# Rectifire__PFC__Evaluation_Board.net
KiCad netlist of a schematic drawn in Altium Designer
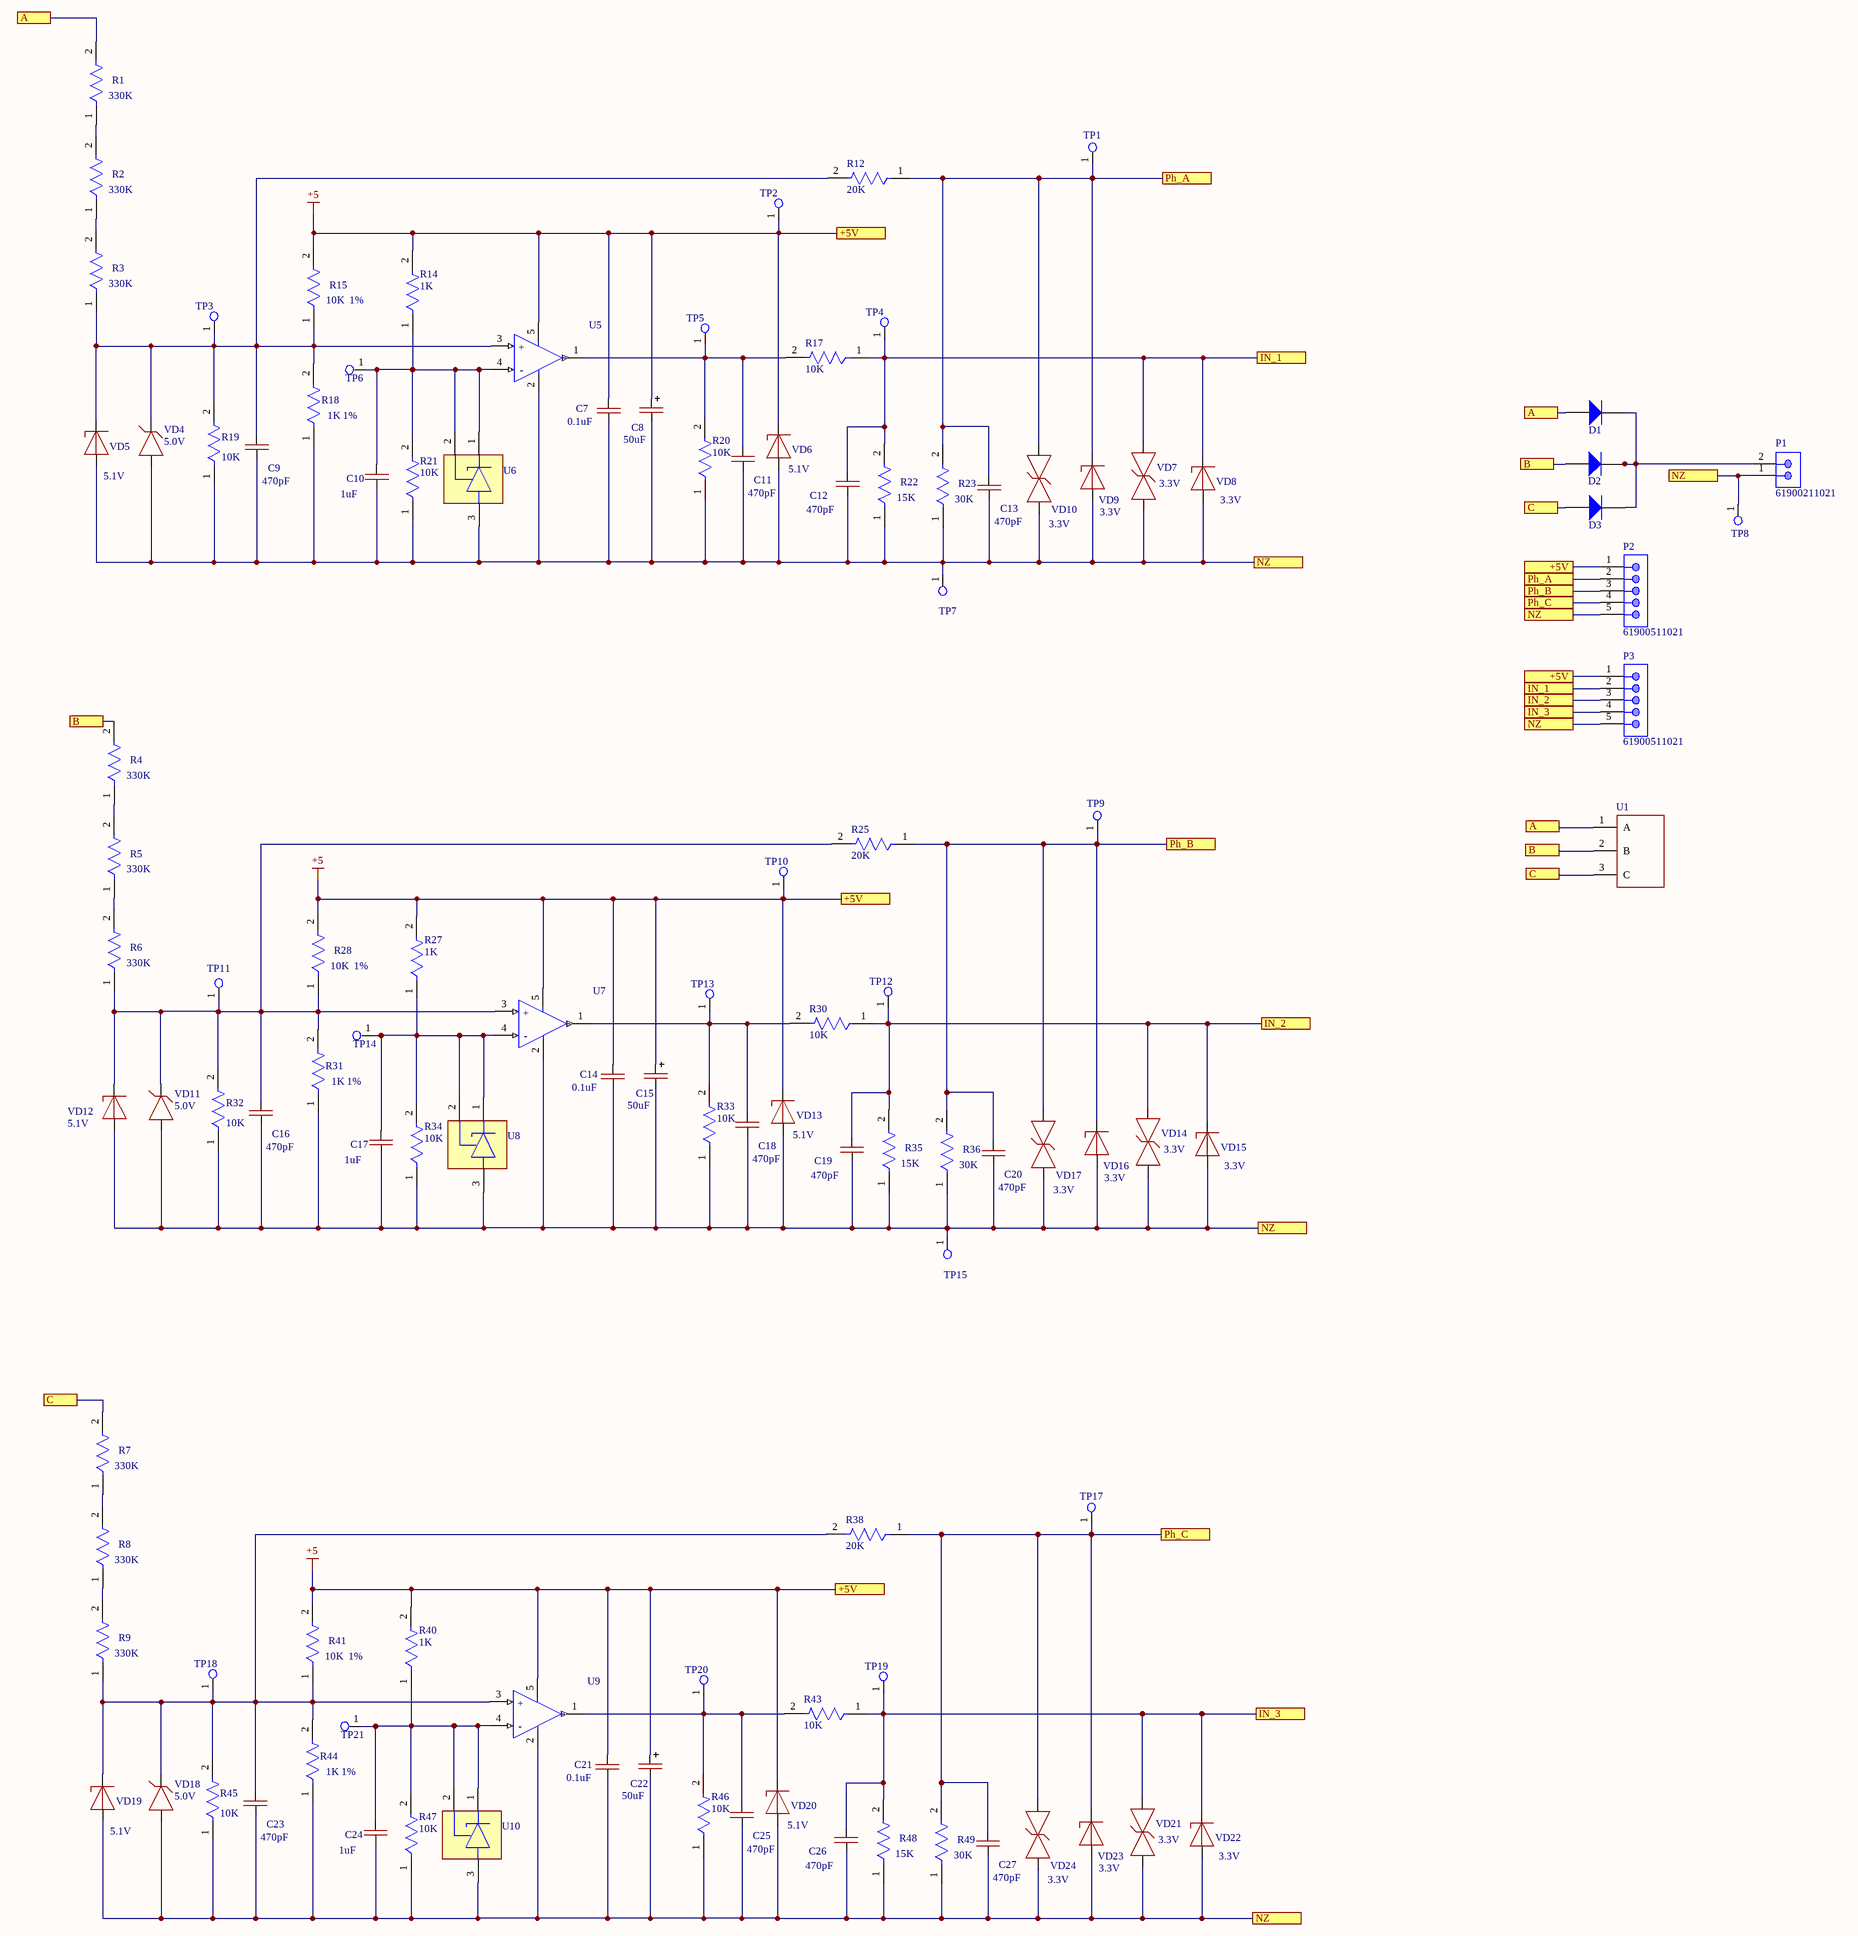
[diagram p0: Rectifire_(PFC)_Evaluation_Board.SchDoc]

(export (version "E")
  (design (tool "Eeschema 10.0.6"))
  (components
    (comp (ref "C7")
      (value "0.1uF")
      (footprint "CAP-0805")
      (libsource (lib "PASSIVE_COMPONENTS") (part "CAP-NON-POLAR"))
    )
    (comp (ref "C8")
      (value "50uF")
      (footprint "CAP-TAN-D")
      (libsource (lib "PASSIVE_COMPONENTS") (part "CAP-POLAR"))
    )
    (comp (ref "C9")
      (value "470pF")
      (footprint "CAP-0805")
      (libsource (lib "PASSIVE_COMPONENTS") (part "CAP-NON-POLAR"))
    )
    (comp (ref "C10")
      (value "1uF")
      (footprint "CAP-0805")
      (libsource (lib "PASSIVE_COMPONENTS") (part "CAP-NON-POLAR"))
    )
    (comp (ref "C11")
      (value "470pF")
      (footprint "CAP-0805")
      (libsource (lib "PASSIVE_COMPONENTS") (part "CAP-NON-POLAR"))
    )
    (comp (ref "C12")
      (value "470pF")
      (footprint "CAP-0805")
      (libsource (lib "PASSIVE_COMPONENTS") (part "CAP-NON-POLAR"))
    )
    (comp (ref "C13")
      (value "470pF")
      (footprint "CAP-0805")
      (libsource (lib "PASSIVE_COMPONENTS") (part "CAP-NON-POLAR"))
    )
    (comp (ref "C14")
      (value "0.1uF")
      (footprint "CAP-0805")
      (libsource (lib "PASSIVE_COMPONENTS") (part "CAP-NON-POLAR"))
    )
    (comp (ref "C15")
      (value "50uF")
      (footprint "CAP-TAN-D")
      (libsource (lib "PASSIVE_COMPONENTS") (part "CAP-POLAR"))
    )
    (comp (ref "C16")
      (value "470pF")
      (footprint "CAP-0805")
      (libsource (lib "PASSIVE_COMPONENTS") (part "CAP-NON-POLAR"))
    )
    (comp (ref "C17")
      (value "1uF")
      (footprint "CAP-0805")
      (libsource (lib "PASSIVE_COMPONENTS") (part "CAP-NON-POLAR"))
    )
    (comp (ref "C18")
      (value "470pF")
      (footprint "CAP-0805")
      (libsource (lib "PASSIVE_COMPONENTS") (part "CAP-NON-POLAR"))
    )
    (comp (ref "C19")
      (value "470pF")
      (footprint "CAP-0805")
      (libsource (lib "PASSIVE_COMPONENTS") (part "CAP-NON-POLAR"))
    )
    (comp (ref "C20")
      (value "470pF")
      (footprint "CAP-0805")
      (libsource (lib "PASSIVE_COMPONENTS") (part "CAP-NON-POLAR"))
    )
    (comp (ref "C21")
      (value "0.1uF")
      (footprint "CAP-0805")
      (libsource (lib "PASSIVE_COMPONENTS") (part "CAP-NON-POLAR"))
    )
    (comp (ref "C22")
      (value "50uF")
      (footprint "CAP-TAN-D")
      (libsource (lib "PASSIVE_COMPONENTS") (part "CAP-POLAR"))
    )
    (comp (ref "C23")
      (value "470pF")
      (footprint "CAP-0805")
      (libsource (lib "PASSIVE_COMPONENTS") (part "CAP-NON-POLAR"))
    )
    (comp (ref "C24")
      (value "1uF")
      (footprint "CAP-0805")
      (libsource (lib "PASSIVE_COMPONENTS") (part "CAP-NON-POLAR"))
    )
    (comp (ref "C25")
      (value "470pF")
      (footprint "CAP-0805")
      (libsource (lib "PASSIVE_COMPONENTS") (part "CAP-NON-POLAR"))
    )
    (comp (ref "C26")
      (value "470pF")
      (footprint "CAP-0805")
      (libsource (lib "PASSIVE_COMPONENTS") (part "CAP-NON-POLAR"))
    )
    (comp (ref "C27")
      (value "470pF")
      (footprint "CAP-0805")
      (libsource (lib "PASSIVE_COMPONENTS") (part "CAP-NON-POLAR"))
    )
    (comp (ref "D1")
      (value "FR-207")
      (footprint "FP-DO-201AD-MFG")
      (description "FR207")
      (libsource (lib "Diodes") (part "FR-207"))
    )
    (comp (ref "D2")
      (value "FR-207")
      (footprint "FP-DO-201AD-MFG")
      (description "FR207")
      (libsource (lib "Diodes") (part "FR-207"))
    )
    (comp (ref "D3")
      (value "FR-207")
      (footprint "FP-DO-201AD-MFG")
      (description "FR207")
      (libsource (lib "Diodes") (part "FR-207"))
    )
    (comp (ref "P1")
      (value "61900211021")
      (footprint "61900211021")
      (description "WR-WTB THT Male Left Angled Bottom Locking Header, pitch 2.54mm, 2p")
      (fields (field (name "PUBLISHER") "Wurth Elektronik"))
      (libsource (lib "Altium_WR-WTB (rev20a)") (part "61900211021"))
    )
    (comp (ref "P2")
      (value "61900511021")
      (footprint "61900511021")
      (description "WR-WTB THT Male Left Angled Bottom Locking Header, pitch 2.54mm, 5p")
      (fields (field (name "PUBLISHER") "Wurth Elektronik"))
      (libsource (lib "Altium_WR-WTB (rev20a)") (part "61900511021"))
    )
    (comp (ref "P3")
      (value "61900511021")
      (footprint "61900511021")
      (description "WR-WTB THT Male Left Angled Bottom Locking Header, pitch 2.54mm, 5p")
      (fields (field (name "PUBLISHER") "Wurth Elektronik"))
      (libsource (lib "Altium_WR-WTB (rev20a)") (part "61900511021"))
    )
    (comp (ref "R1")
      (value "330K")
      (footprint "RES-1206")
      (description "10K")
      (libsource (lib "PASSIVE_COMPONENTS") (part "RES-CONST"))
    )
    (comp (ref "R2")
      (value "330K")
      (footprint "RES-1206")
      (description "10K")
      (libsource (lib "PASSIVE_COMPONENTS") (part "RES-CONST"))
    )
    (comp (ref "R3")
      (value "330K")
      (footprint "RES-1206")
      (description "10K")
      (libsource (lib "PASSIVE_COMPONENTS") (part "RES-CONST"))
    )
    (comp (ref "R4")
      (value "330K")
      (footprint "RES-1206")
      (description "10K")
      (libsource (lib "PASSIVE_COMPONENTS") (part "RES-CONST"))
    )
    (comp (ref "R5")
      (value "330K")
      (footprint "RES-1206")
      (description "10K")
      (libsource (lib "PASSIVE_COMPONENTS") (part "RES-CONST"))
    )
    (comp (ref "R6")
      (value "330K")
      (footprint "RES-1206")
      (description "10K")
      (libsource (lib "PASSIVE_COMPONENTS") (part "RES-CONST"))
    )
    (comp (ref "R7")
      (value "330K")
      (footprint "RES-1206")
      (description "10K")
      (libsource (lib "PASSIVE_COMPONENTS") (part "RES-CONST"))
    )
    (comp (ref "R8")
      (value "330K")
      (footprint "RES-1206")
      (description "10K")
      (libsource (lib "PASSIVE_COMPONENTS") (part "RES-CONST"))
    )
    (comp (ref "R9")
      (value "330K")
      (footprint "RES-1206")
      (description "10K")
      (libsource (lib "PASSIVE_COMPONENTS") (part "RES-CONST"))
    )
    (comp (ref "R12")
      (value "20K")
      (footprint "RES-0805")
      (libsource (lib "PASSIVE_COMPONENTS") (part "RES-CONST"))
    )
    (comp (ref "R14")
      (value "1K")
      (footprint "RES-0805")
      (description "4.7K")
      (libsource (lib "PASSIVE_COMPONENTS") (part "RES-CONST"))
    )
    (comp (ref "R15")
      (value "10K  1%")
      (footprint "RES-0805")
      (description "10K")
      (libsource (lib "PASSIVE_COMPONENTS") (part "RES-CONST"))
    )
    (comp (ref "R17")
      (value "10K")
      (footprint "RES-0805")
      (libsource (lib "PASSIVE_COMPONENTS") (part "RES-CONST"))
    )
    (comp (ref "R18")
      (value "1K 1%")
      (footprint "RES-0805")
      (description "1K")
      (libsource (lib "PASSIVE_COMPONENTS") (part "RES-CONST"))
    )
    (comp (ref "R19")
      (value "10K")
      (footprint "RES_SMD_1210_IPC_B")
      (libsource (lib "PASSIVE_COMPONENTS") (part "RES_1210"))
    )
    (comp (ref "R20")
      (value "10K")
      (footprint "RES-0805")
      (libsource (lib "PASSIVE_COMPONENTS") (part "RES-CONST"))
    )
    (comp (ref "R21")
      (value "10K")
      (footprint "RES-0805")
      (libsource (lib "PASSIVE_COMPONENTS") (part "RES-CONST"))
    )
    (comp (ref "R22")
      (value "15K")
      (footprint "RES-0805")
      (libsource (lib "PASSIVE_COMPONENTS") (part "RES-CONST"))
    )
    (comp (ref "R23")
      (value "30K")
      (footprint "RES-0805")
      (libsource (lib "PASSIVE_COMPONENTS") (part "RES-CONST"))
    )
    (comp (ref "R25")
      (value "20K")
      (footprint "RES-0805")
      (libsource (lib "PASSIVE_COMPONENTS") (part "RES-CONST"))
    )
    (comp (ref "R27")
      (value "1K")
      (footprint "RES-0805")
      (description "4.7K")
      (libsource (lib "PASSIVE_COMPONENTS") (part "RES-CONST"))
    )
    (comp (ref "R28")
      (value "10K  1%")
      (footprint "RES-0805")
      (description "10K")
      (libsource (lib "PASSIVE_COMPONENTS") (part "RES-CONST"))
    )
    (comp (ref "R30")
      (value "10K")
      (footprint "RES-0805")
      (libsource (lib "PASSIVE_COMPONENTS") (part "RES-CONST"))
    )
    (comp (ref "R31")
      (value "1K 1%")
      (footprint "RES-0805")
      (description "1K")
      (libsource (lib "PASSIVE_COMPONENTS") (part "RES-CONST"))
    )
    (comp (ref "R32")
      (value "10K")
      (footprint "RES_SMD_1210_IPC_B")
      (libsource (lib "PASSIVE_COMPONENTS") (part "RES_1210"))
    )
    (comp (ref "R33")
      (value "10K")
      (footprint "RES-0805")
      (libsource (lib "PASSIVE_COMPONENTS") (part "RES-CONST"))
    )
    (comp (ref "R34")
      (value "10K")
      (footprint "RES-0805")
      (libsource (lib "PASSIVE_COMPONENTS") (part "RES-CONST"))
    )
    (comp (ref "R35")
      (value "15K")
      (footprint "RES-0805")
      (libsource (lib "PASSIVE_COMPONENTS") (part "RES-CONST"))
    )
    (comp (ref "R36")
      (value "30K")
      (footprint "RES-0805")
      (libsource (lib "PASSIVE_COMPONENTS") (part "RES-CONST"))
    )
    (comp (ref "R38")
      (value "20K")
      (footprint "RES-0805")
      (libsource (lib "PASSIVE_COMPONENTS") (part "RES-CONST"))
    )
    (comp (ref "R40")
      (value "1K")
      (footprint "RES-0805")
      (description "4.7K")
      (libsource (lib "PASSIVE_COMPONENTS") (part "RES-CONST"))
    )
    (comp (ref "R41")
      (value "10K  1%")
      (footprint "RES-0805")
      (description "10K")
      (libsource (lib "PASSIVE_COMPONENTS") (part "RES-CONST"))
    )
    (comp (ref "R43")
      (value "10K")
      (footprint "RES-0805")
      (libsource (lib "PASSIVE_COMPONENTS") (part "RES-CONST"))
    )
    (comp (ref "R44")
      (value "1K 1%")
      (footprint "RES-0805")
      (description "1K")
      (libsource (lib "PASSIVE_COMPONENTS") (part "RES-CONST"))
    )
    (comp (ref "R45")
      (value "10K")
      (footprint "RES_SMD_1210_IPC_B")
      (libsource (lib "PASSIVE_COMPONENTS") (part "RES_1210"))
    )
    (comp (ref "R46")
      (value "10K")
      (footprint "RES-0805")
      (libsource (lib "PASSIVE_COMPONENTS") (part "RES-CONST"))
    )
    (comp (ref "R47")
      (value "10K")
      (footprint "RES-0805")
      (libsource (lib "PASSIVE_COMPONENTS") (part "RES-CONST"))
    )
    (comp (ref "R48")
      (value "15K")
      (footprint "RES-0805")
      (libsource (lib "PASSIVE_COMPONENTS") (part "RES-CONST"))
    )
    (comp (ref "R49")
      (value "30K")
      (footprint "RES-0805")
      (libsource (lib "PASSIVE_COMPONENTS") (part "RES-CONST"))
    )
    (comp (ref "TP1")
      (value "Test_Point_PCB")
      (footprint "Test_Point")
      (description "Test_Point")
      (libsource (lib "Connectors") (part "TP_PCB?"))
    )
    (comp (ref "TP2")
      (value "Test_Point_PCB")
      (footprint "Test_Point")
      (description "Test_Point")
      (libsource (lib "Connectors") (part "TP_PCB?"))
    )
    (comp (ref "TP3")
      (value "Test_Point_PCB")
      (footprint "Test_Point")
      (description "Test_Point")
      (libsource (lib "Connectors") (part "TP_PCB?"))
    )
    (comp (ref "TP4")
      (value "Test_Point_PCB")
      (footprint "Test_Point")
      (description "Test_Point")
      (libsource (lib "Connectors") (part "TP_PCB?"))
    )
    (comp (ref "TP5")
      (value "Test_Point_PCB")
      (footprint "Test_Point")
      (description "Test_Point")
      (libsource (lib "Connectors") (part "TP_PCB?"))
    )
    (comp (ref "TP6")
      (value "Test_Point_PCB")
      (footprint "Test_Point")
      (description "Test_Point")
      (libsource (lib "Connectors") (part "TP_PCB?"))
    )
    (comp (ref "TP7")
      (value "Test_Point_PCB")
      (footprint "Test_Point")
      (description "Test_Point")
      (libsource (lib "Connectors") (part "TP_PCB?"))
    )
    (comp (ref "TP8")
      (value "Test_Point_PCB")
      (footprint "Test_Point")
      (description "Test_Point")
      (libsource (lib "Connectors") (part "TP_PCB?"))
    )
    (comp (ref "TP9")
      (value "Test_Point_PCB")
      (footprint "Test_Point")
      (description "Test_Point")
      (libsource (lib "Connectors") (part "TP_PCB?"))
    )
    (comp (ref "TP10")
      (value "Test_Point_PCB")
      (footprint "Test_Point")
      (description "Test_Point")
      (libsource (lib "Connectors") (part "TP_PCB?"))
    )
    (comp (ref "TP11")
      (value "Test_Point_PCB")
      (footprint "Test_Point")
      (description "Test_Point")
      (libsource (lib "Connectors") (part "TP_PCB?"))
    )
    (comp (ref "TP12")
      (value "Test_Point_PCB")
      (footprint "Test_Point")
      (description "Test_Point")
      (libsource (lib "Connectors") (part "TP_PCB?"))
    )
    (comp (ref "TP13")
      (value "Test_Point_PCB")
      (footprint "Test_Point")
      (description "Test_Point")
      (libsource (lib "Connectors") (part "TP_PCB?"))
    )
    (comp (ref "TP14")
      (value "Test_Point_PCB")
      (footprint "Test_Point")
      (description "Test_Point")
      (libsource (lib "Connectors") (part "TP_PCB?"))
    )
    (comp (ref "TP15")
      (value "Test_Point_PCB")
      (footprint "Test_Point")
      (description "Test_Point")
      (libsource (lib "Connectors") (part "TP_PCB?"))
    )
    (comp (ref "TP17")
      (value "Test_Point_PCB")
      (footprint "Test_Point")
      (description "Test_Point")
      (libsource (lib "Connectors") (part "TP_PCB?"))
    )
    (comp (ref "TP18")
      (value "~")
      (footprint "Test_Point")
      (description "Test_Point")
      (libsource (lib "Connectors") (part "TP_PCB?"))
    )
    (comp (ref "TP19")
      (value "~")
      (footprint "Test_Point")
      (description "Test_Point")
      (libsource (lib "Connectors") (part "TP_PCB?"))
    )
    (comp (ref "TP20")
      (value "Test_Point_PCB")
      (footprint "Test_Point")
      (description "Test_Point")
      (libsource (lib "Connectors") (part "TP_PCB?"))
    )
    (comp (ref "TP21")
      (value "Test_Point_PCB")
      (footprint "Test_Point")
      (description "Test_Point")
      (libsource (lib "Connectors") (part "TP_PCB?"))
    )
    (comp (ref "U1") (value "~") (footprint "MDS100") (libsource (lib "MDS100") (part "MDS100")))
    (comp (ref "U5")
      (value "~")
      (footprint "SOT-23-5")
      (description "IC OPAMP GP 1 CIRCUIT SOT23-5")
      (fields (field (name "VOLTAGE") "6V"))
      (libsource (lib "Integrated_Circuts") (part "MCP6001T"))
    )
    (comp (ref "U6")
      (value "TL431")
      (footprint "TL431_SOT-23-3(A)")
      (description "TL431_SOT-23-3")
      (libsource (lib "Diodes") (part "TL431_SOT-23-3"))
    )
    (comp (ref "U7")
      (value "~")
      (footprint "SOT-23-5")
      (description "IC OPAMP GP 1 CIRCUIT SOT23-5")
      (fields (field (name "VOLTAGE") "6V"))
      (libsource (lib "Integrated_Circuts") (part "MCP6001T"))
    )
    (comp (ref "U8")
      (value "TL431")
      (footprint "TL431_SOT-23-3(A)")
      (description "TL431_SOT-23-3")
      (libsource (lib "Diodes") (part "TL431_SOT-23-3"))
    )
    (comp (ref "U9")
      (value "~")
      (footprint "SOT-23-5")
      (description "IC OPAMP GP 1 CIRCUIT SOT23-5")
      (fields (field (name "VOLTAGE") "6V"))
      (libsource (lib "Integrated_Circuts") (part "MCP6001T"))
    )
    (comp (ref "U10")
      (value "TL431")
      (footprint "TL431_SOT-23-3(A)")
      (description "TL431_SOT-23-3")
      (libsource (lib "Diodes") (part "TL431_SOT-23-3"))
    )
    (comp (ref "VD4") (value "5.0V") (footprint "SOD-323") (libsource (lib "Diodes") (part "SMBJ15A")))
    (comp (ref "VD5") (value "5.1V") (footprint "DIOD-SOD123-2_V") (libsource (lib "Diodes") (part "ZENER")))
    (comp (ref "VD6") (value "5.1V") (footprint "DIOD-SOD123-2_V") (libsource (lib "Diodes") (part "ZENER")))
    (comp (ref "VD7") (value "3.3V") (footprint "DO-214AA") (libsource (lib "Diodes") (part "Suppressor")))
    (comp (ref "VD8") (value "3.3V") (footprint "DIOD-SOD123-2_V") (libsource (lib "Diodes") (part "ZENER")))
    (comp (ref "VD9") (value "3.3V") (footprint "DIOD-SOD123-2_V") (libsource (lib "Diodes") (part "ZENER")))
    (comp (ref "VD10") (value "3.3V") (footprint "DO-214AA") (libsource (lib "Diodes") (part "Suppressor")))
    (comp (ref "VD11") (value "5.0V") (footprint "SOD-323") (libsource (lib "Diodes") (part "SMBJ15A")))
    (comp (ref "VD12") (value "5.1V") (footprint "DIOD-SOD123-2_V") (libsource (lib "Diodes") (part "ZENER")))
    (comp (ref "VD13") (value "5.1V") (footprint "DIOD-SOD123-2_V") (libsource (lib "Diodes") (part "ZENER")))
    (comp (ref "VD14") (value "3.3V") (footprint "DO-214AA") (libsource (lib "Diodes") (part "Suppressor")))
    (comp (ref "VD15") (value "3.3V") (footprint "DIOD-SOD123-2_V") (libsource (lib "Diodes") (part "ZENER")))
    (comp (ref "VD16") (value "3.3V") (footprint "DIOD-SOD123-2_V") (libsource (lib "Diodes") (part "ZENER")))
    (comp (ref "VD17") (value "3.3V") (footprint "DO-214AA") (libsource (lib "Diodes") (part "Suppressor")))
    (comp (ref "VD18") (value "5.0V") (footprint "SOD-323") (libsource (lib "Diodes") (part "SMBJ15A")))
    (comp (ref "VD19") (value "5.1V") (footprint "DIOD-SOD123-2_V") (libsource (lib "Diodes") (part "ZENER")))
    (comp (ref "VD20") (value "5.1V") (footprint "DIOD-SOD123-2_V") (libsource (lib "Diodes") (part "ZENER")))
    (comp (ref "VD21") (value "3.3V") (footprint "DO-214AA") (libsource (lib "Diodes") (part "Suppressor")))
    (comp (ref "VD22") (value "3.3V") (footprint "DIOD-SOD123-2_V") (libsource (lib "Diodes") (part "ZENER")))
    (comp (ref "VD23") (value "3.3V") (footprint "DIOD-SOD123-2_V") (libsource (lib "Diodes") (part "ZENER")))
    (comp (ref "VD24") (value "3.3V") (footprint "DO-214AA") (libsource (lib "Diodes") (part "Suppressor")))
  )
  (nets
    (net (code "1") (name "+5") (class "Default")
      (node (ref "C14") (pin "2") (pinfunction "2_2") (pintype "passive"))
      (node (ref "C15") (pin "1") (pinfunction "+_1") (pintype "passive"))
      (node (ref "C21") (pin "2") (pinfunction "2_2") (pintype "passive"))
      (node (ref "C22") (pin "1") (pinfunction "+_1") (pintype "passive"))
      (node (ref "C7") (pin "2") (pinfunction "2_2") (pintype "passive"))
      (node (ref "C8") (pin "1") (pinfunction "+_1") (pintype "passive"))
      (node (ref "P2") (pin "1") (pinfunction "1_1") (pintype "passive"))
      (node (ref "P3") (pin "1") (pinfunction "1_1") (pintype "passive"))
      (node (ref "R14") (pin "2") (pinfunction "2_2") (pintype "passive"))
      (node (ref "R15") (pin "2") (pinfunction "2_2") (pintype "passive"))
      (node (ref "R27") (pin "2") (pinfunction "2_2") (pintype "passive"))
      (node (ref "R28") (pin "2") (pinfunction "2_2") (pintype "passive"))
      (node (ref "R40") (pin "2") (pinfunction "2_2") (pintype "passive"))
      (node (ref "R41") (pin "2") (pinfunction "2_2") (pintype "passive"))
      (node (ref "TP10") (pin "1") (pinfunction "G9_1") (pintype "passive"))
      (node (ref "TP2") (pin "1") (pinfunction "G9_1") (pintype "passive"))
      (node (ref "U5") (pin "5") (pinfunction "VDD_5") (pintype "power_in"))
      (node (ref "U7") (pin "5") (pinfunction "VDD_5") (pintype "power_in"))
      (node (ref "U9") (pin "5") (pinfunction "VDD_5") (pintype "power_in"))
      (node (ref "VD13") (pin "1") (pinfunction "C_1") (pintype "passive"))
      (node (ref "VD20") (pin "1") (pinfunction "C_1") (pintype "passive"))
      (node (ref "VD6") (pin "1") (pinfunction "C_1") (pintype "passive"))
    )
    (net (code "2") (name "/A") (class "Default")
      (node (ref "D1") (pin "2") (pinfunction "A_2") (pintype "passive"))
      (node (ref "R1") (pin "2") (pinfunction "2_2") (pintype "passive"))
      (node (ref "U1") (pin "1") (pinfunction "A_1") (pintype "tri_state"))
    )
    (net (code "3") (name "/B") (class "Default")
      (node (ref "D2") (pin "2") (pinfunction "A_2") (pintype "passive"))
      (node (ref "R4") (pin "2") (pinfunction "2_2") (pintype "passive"))
      (node (ref "U1") (pin "2") (pinfunction "B_2") (pintype "tri_state"))
    )
    (net (code "4") (name "/C") (class "Default")
      (node (ref "D3") (pin "2") (pinfunction "A_2") (pintype "passive"))
      (node (ref "R7") (pin "2") (pinfunction "2_2") (pintype "passive"))
      (node (ref "U1") (pin "3") (pinfunction "C_3") (pintype "tri_state"))
    )
    (net (code "5") (name "/IN_1") (class "Default")
      (node (ref "C12") (pin "2") (pinfunction "2_2") (pintype "passive"))
      (node (ref "P3") (pin "2") (pinfunction "2_2") (pintype "passive"))
      (node (ref "R17") (pin "1") (pinfunction "1_1") (pintype "passive"))
      (node (ref "R22") (pin "2") (pinfunction "2_2") (pintype "passive"))
      (node (ref "TP4") (pin "1") (pinfunction "G9_1") (pintype "passive"))
      (node (ref "VD7") (pin "2") (pinfunction "A_2") (pintype "passive"))
      (node (ref "VD8") (pin "1") (pinfunction "C_1") (pintype "passive"))
    )
    (net (code "6") (name "/IN_2") (class "Default")
      (node (ref "C19") (pin "2") (pinfunction "2_2") (pintype "passive"))
      (node (ref "P3") (pin "3") (pinfunction "3_3") (pintype "passive"))
      (node (ref "R30") (pin "1") (pinfunction "1_1") (pintype "passive"))
      (node (ref "R35") (pin "2") (pinfunction "2_2") (pintype "passive"))
      (node (ref "TP12") (pin "1") (pinfunction "G9_1") (pintype "passive"))
      (node (ref "VD14") (pin "2") (pinfunction "A_2") (pintype "passive"))
      (node (ref "VD15") (pin "1") (pinfunction "C_1") (pintype "passive"))
    )
    (net (code "7") (name "/IN_3") (class "Default")
      (node (ref "C26") (pin "2") (pinfunction "2_2") (pintype "passive"))
      (node (ref "P3") (pin "4") (pinfunction "4_4") (pintype "passive"))
      (node (ref "R43") (pin "1") (pinfunction "1_1") (pintype "passive"))
      (node (ref "R48") (pin "2") (pinfunction "2_2") (pintype "passive"))
      (node (ref "TP19") (pin "1") (pinfunction "G9_1") (pintype "passive"))
      (node (ref "VD21") (pin "2") (pinfunction "A_2") (pintype "passive"))
      (node (ref "VD22") (pin "1") (pinfunction "C_1") (pintype "passive"))
    )
    (net (code "8") (name "/NZ") (class "Default")
      (node (ref "C10") (pin "1") (pinfunction "1_1") (pintype "passive"))
      (node (ref "C11") (pin "1") (pinfunction "1_1") (pintype "passive"))
      (node (ref "C12") (pin "1") (pinfunction "1_1") (pintype "passive"))
      (node (ref "C13") (pin "1") (pinfunction "1_1") (pintype "passive"))
      (node (ref "C14") (pin "1") (pinfunction "1_1") (pintype "passive"))
      (node (ref "C15") (pin "2") (pinfunction "-_2") (pintype "passive"))
      (node (ref "C16") (pin "1") (pinfunction "1_1") (pintype "passive"))
      (node (ref "C17") (pin "1") (pinfunction "1_1") (pintype "passive"))
      (node (ref "C18") (pin "1") (pinfunction "1_1") (pintype "passive"))
      (node (ref "C19") (pin "1") (pinfunction "1_1") (pintype "passive"))
      (node (ref "C20") (pin "1") (pinfunction "1_1") (pintype "passive"))
      (node (ref "C21") (pin "1") (pinfunction "1_1") (pintype "passive"))
      (node (ref "C22") (pin "2") (pinfunction "-_2") (pintype "passive"))
      (node (ref "C23") (pin "1") (pinfunction "1_1") (pintype "passive"))
      (node (ref "C24") (pin "1") (pinfunction "1_1") (pintype "passive"))
      (node (ref "C25") (pin "1") (pinfunction "1_1") (pintype "passive"))
      (node (ref "C26") (pin "1") (pinfunction "1_1") (pintype "passive"))
      (node (ref "C27") (pin "1") (pinfunction "1_1") (pintype "passive"))
      (node (ref "C7") (pin "1") (pinfunction "1_1") (pintype "passive"))
      (node (ref "C8") (pin "2") (pinfunction "-_2") (pintype "passive"))
      (node (ref "C9") (pin "1") (pinfunction "1_1") (pintype "passive"))
      (node (ref "P1") (pin "1") (pinfunction "1_1") (pintype "passive"))
      (node (ref "P2") (pin "5") (pinfunction "5_5") (pintype "passive"))
      (node (ref "P3") (pin "5") (pinfunction "5_5") (pintype "passive"))
      (node (ref "R18") (pin "1") (pinfunction "1_1") (pintype "passive"))
      (node (ref "R19") (pin "1") (pinfunction "1_1") (pintype "passive"))
      (node (ref "R20") (pin "1") (pinfunction "1_1") (pintype "passive"))
      (node (ref "R21") (pin "1") (pinfunction "1_1") (pintype "passive"))
      (node (ref "R22") (pin "1") (pinfunction "1_1") (pintype "passive"))
      (node (ref "R23") (pin "1") (pinfunction "1_1") (pintype "passive"))
      (node (ref "R31") (pin "1") (pinfunction "1_1") (pintype "passive"))
      (node (ref "R32") (pin "1") (pinfunction "1_1") (pintype "passive"))
      (node (ref "R33") (pin "1") (pinfunction "1_1") (pintype "passive"))
      (node (ref "R34") (pin "1") (pinfunction "1_1") (pintype "passive"))
      (node (ref "R35") (pin "1") (pinfunction "1_1") (pintype "passive"))
      (node (ref "R36") (pin "1") (pinfunction "1_1") (pintype "passive"))
      (node (ref "R44") (pin "1") (pinfunction "1_1") (pintype "passive"))
      (node (ref "R45") (pin "1") (pinfunction "1_1") (pintype "passive"))
      (node (ref "R46") (pin "1") (pinfunction "1_1") (pintype "passive"))
      (node (ref "R47") (pin "1") (pinfunction "1_1") (pintype "passive"))
      (node (ref "R48") (pin "1") (pinfunction "1_1") (pintype "passive"))
      (node (ref "R49") (pin "1") (pinfunction "1_1") (pintype "passive"))
      (node (ref "TP15") (pin "1") (pinfunction "G9_1") (pintype "passive"))
      (node (ref "TP7") (pin "1") (pinfunction "G9_1") (pintype "passive"))
      (node (ref "TP8") (pin "1") (pinfunction "G9_1") (pintype "passive"))
      (node (ref "U10") (pin "3") (pinfunction "A_3") (pintype "passive"))
      (node (ref "U5") (pin "2") (pinfunction "VSS_2") (pintype "power_in"))
      (node (ref "U6") (pin "3") (pinfunction "A_3") (pintype "passive"))
      (node (ref "U7") (pin "2") (pinfunction "VSS_2") (pintype "power_in"))
      (node (ref "U8") (pin "3") (pinfunction "A_3") (pintype "passive"))
      (node (ref "U9") (pin "2") (pinfunction "VSS_2") (pintype "power_in"))
      (node (ref "VD10") (pin "1") (pinfunction "C_1") (pintype "passive"))
      (node (ref "VD11") (pin "1") (pinfunction "A_1") (pintype "passive"))
      (node (ref "VD12") (pin "2") (pinfunction "A_2") (pintype "passive"))
      (node (ref "VD13") (pin "2") (pinfunction "A_2") (pintype "passive"))
      (node (ref "VD14") (pin "1") (pinfunction "C_1") (pintype "passive"))
      (node (ref "VD15") (pin "2") (pinfunction "A_2") (pintype "passive"))
      (node (ref "VD16") (pin "2") (pinfunction "A_2") (pintype "passive"))
      (node (ref "VD17") (pin "1") (pinfunction "C_1") (pintype "passive"))
      (node (ref "VD18") (pin "1") (pinfunction "A_1") (pintype "passive"))
      (node (ref "VD19") (pin "2") (pinfunction "A_2") (pintype "passive"))
      (node (ref "VD20") (pin "2") (pinfunction "A_2") (pintype "passive"))
      (node (ref "VD21") (pin "1") (pinfunction "C_1") (pintype "passive"))
      (node (ref "VD22") (pin "2") (pinfunction "A_2") (pintype "passive"))
      (node (ref "VD23") (pin "2") (pinfunction "A_2") (pintype "passive"))
      (node (ref "VD24") (pin "1") (pinfunction "C_1") (pintype "passive"))
      (node (ref "VD4") (pin "1") (pinfunction "A_1") (pintype "passive"))
      (node (ref "VD5") (pin "2") (pinfunction "A_2") (pintype "passive"))
      (node (ref "VD6") (pin "2") (pinfunction "A_2") (pintype "passive"))
      (node (ref "VD7") (pin "1") (pinfunction "C_1") (pintype "passive"))
      (node (ref "VD8") (pin "2") (pinfunction "A_2") (pintype "passive"))
      (node (ref "VD9") (pin "2") (pinfunction "A_2") (pintype "passive"))
    )
    (net (code "9") (name "/Ph_A") (class "Default")
      (node (ref "C13") (pin "2") (pinfunction "2_2") (pintype "passive"))
      (node (ref "P2") (pin "2") (pinfunction "2_2") (pintype "passive"))
      (node (ref "R12") (pin "1") (pinfunction "1_1") (pintype "passive"))
      (node (ref "R23") (pin "2") (pinfunction "2_2") (pintype "passive"))
      (node (ref "TP1") (pin "1") (pinfunction "G9_1") (pintype "passive"))
      (node (ref "VD10") (pin "2") (pinfunction "A_2") (pintype "passive"))
      (node (ref "VD9") (pin "1") (pinfunction "C_1") (pintype "passive"))
    )
    (net (code "10") (name "/Ph_B") (class "Default")
      (node (ref "C20") (pin "2") (pinfunction "2_2") (pintype "passive"))
      (node (ref "P2") (pin "3") (pinfunction "3_3") (pintype "passive"))
      (node (ref "R25") (pin "1") (pinfunction "1_1") (pintype "passive"))
      (node (ref "R36") (pin "2") (pinfunction "2_2") (pintype "passive"))
      (node (ref "TP9") (pin "1") (pinfunction "G9_1") (pintype "passive"))
      (node (ref "VD16") (pin "1") (pinfunction "C_1") (pintype "passive"))
      (node (ref "VD17") (pin "2") (pinfunction "A_2") (pintype "passive"))
    )
    (net (code "11") (name "/Ph_C") (class "Default")
      (node (ref "C27") (pin "2") (pinfunction "2_2") (pintype "passive"))
      (node (ref "P2") (pin "4") (pinfunction "4_4") (pintype "passive"))
      (node (ref "R38") (pin "1") (pinfunction "1_1") (pintype "passive"))
      (node (ref "R49") (pin "2") (pinfunction "2_2") (pintype "passive"))
      (node (ref "TP17") (pin "1") (pinfunction "G9_1") (pintype "passive"))
      (node (ref "VD23") (pin "1") (pinfunction "C_1") (pintype "passive"))
      (node (ref "VD24") (pin "2") (pinfunction "A_2") (pintype "passive"))
    )
    (net (code "12") (name "Net-(D1-K)") (class "Default")
      (node (ref "D1") (pin "1") (pinfunction "K_1") (pintype "passive"))
      (node (ref "D2") (pin "1") (pinfunction "K_1") (pintype "passive"))
      (node (ref "D3") (pin "1") (pinfunction "K_1") (pintype "passive"))
      (node (ref "P1") (pin "2") (pinfunction "2_2") (pintype "passive"))
    )
    (net (code "13") (name "Net-(R1-Pad1)") (class "Default")
      (node (ref "R1") (pin "1") (pinfunction "1_1") (pintype "passive"))
      (node (ref "R2") (pin "2") (pinfunction "2_2") (pintype "passive"))
    )
    (net (code "14") (name "Net-(R2-Pad1)") (class "Default")
      (node (ref "R2") (pin "1") (pinfunction "1_1") (pintype "passive"))
      (node (ref "R3") (pin "2") (pinfunction "2_2") (pintype "passive"))
    )
    (net (code "15") (name "Net-(R4-Pad1)") (class "Default")
      (node (ref "R4") (pin "1") (pinfunction "1_1") (pintype "passive"))
      (node (ref "R5") (pin "2") (pinfunction "2_2") (pintype "passive"))
    )
    (net (code "16") (name "Net-(R5-Pad1)") (class "Default")
      (node (ref "R5") (pin "1") (pinfunction "1_1") (pintype "passive"))
      (node (ref "R6") (pin "2") (pinfunction "2_2") (pintype "passive"))
    )
    (net (code "17") (name "Net-(R7-Pad1)") (class "Default")
      (node (ref "R7") (pin "1") (pinfunction "1_1") (pintype "passive"))
      (node (ref "R8") (pin "2") (pinfunction "2_2") (pintype "passive"))
    )
    (net (code "18") (name "Net-(R8-Pad1)") (class "Default")
      (node (ref "R8") (pin "1") (pinfunction "1_1") (pintype "passive"))
      (node (ref "R9") (pin "2") (pinfunction "2_2") (pintype "passive"))
    )
    (net (code "19") (name "Net-(TP3-G9)") (class "Default")
      (node (ref "C9") (pin "2") (pinfunction "2_2") (pintype "passive"))
      (node (ref "R12") (pin "2") (pinfunction "2_2") (pintype "passive"))
      (node (ref "R15") (pin "1") (pinfunction "1_1") (pintype "passive"))
      (node (ref "R18") (pin "2") (pinfunction "2_2") (pintype "passive"))
      (node (ref "R19") (pin "2") (pinfunction "2_2") (pintype "passive"))
      (node (ref "R3") (pin "1") (pinfunction "1_1") (pintype "passive"))
      (node (ref "TP3") (pin "1") (pinfunction "G9_1") (pintype "passive"))
      (node (ref "U5") (pin "3") (pinfunction "VIN+_3") (pintype "input"))
      (node (ref "VD4") (pin "2") (pinfunction "C_2") (pintype "passive"))
      (node (ref "VD5") (pin "1") (pinfunction "C_1") (pintype "passive"))
    )
    (net (code "20") (name "Net-(TP5-G9)") (class "Default")
      (node (ref "C11") (pin "2") (pinfunction "2_2") (pintype "passive"))
      (node (ref "R17") (pin "2") (pinfunction "2_2") (pintype "passive"))
      (node (ref "R20") (pin "2") (pinfunction "2_2") (pintype "passive"))
      (node (ref "TP5") (pin "1") (pinfunction "G9_1") (pintype "passive"))
      (node (ref "U5") (pin "1") (pinfunction "VOUT_1") (pintype "output"))
    )
    (net (code "21") (name "Net-(TP6-G9)") (class "Default")
      (node (ref "C10") (pin "2") (pinfunction "2_2") (pintype "passive"))
      (node (ref "R14") (pin "1") (pinfunction "1_1") (pintype "passive"))
      (node (ref "R21") (pin "2") (pinfunction "2_2") (pintype "passive"))
      (node (ref "TP6") (pin "1") (pinfunction "G9_1") (pintype "passive"))
      (node (ref "U5") (pin "4") (pinfunction "VIN-_4") (pintype "input"))
      (node (ref "U6") (pin "1") (pinfunction "C_1") (pintype "passive"))
      (node (ref "U6") (pin "2") (pinfunction "REF_2") (pintype "passive"))
    )
    (net (code "22") (name "Net-(TP11-G9)") (class "Default")
      (node (ref "C16") (pin "2") (pinfunction "2_2") (pintype "passive"))
      (node (ref "R25") (pin "2") (pinfunction "2_2") (pintype "passive"))
      (node (ref "R28") (pin "1") (pinfunction "1_1") (pintype "passive"))
      (node (ref "R31") (pin "2") (pinfunction "2_2") (pintype "passive"))
      (node (ref "R32") (pin "2") (pinfunction "2_2") (pintype "passive"))
      (node (ref "R6") (pin "1") (pinfunction "1_1") (pintype "passive"))
      (node (ref "TP11") (pin "1") (pinfunction "G9_1") (pintype "passive"))
      (node (ref "U7") (pin "3") (pinfunction "VIN+_3") (pintype "input"))
      (node (ref "VD11") (pin "2") (pinfunction "C_2") (pintype "passive"))
      (node (ref "VD12") (pin "1") (pinfunction "C_1") (pintype "passive"))
    )
    (net (code "23") (name "Net-(TP13-G9)") (class "Default")
      (node (ref "C18") (pin "2") (pinfunction "2_2") (pintype "passive"))
      (node (ref "R30") (pin "2") (pinfunction "2_2") (pintype "passive"))
      (node (ref "R33") (pin "2") (pinfunction "2_2") (pintype "passive"))
      (node (ref "TP13") (pin "1") (pinfunction "G9_1") (pintype "passive"))
      (node (ref "U7") (pin "1") (pinfunction "VOUT_1") (pintype "output"))
    )
    (net (code "24") (name "Net-(TP14-G9)") (class "Default")
      (node (ref "C17") (pin "2") (pinfunction "2_2") (pintype "passive"))
      (node (ref "R27") (pin "1") (pinfunction "1_1") (pintype "passive"))
      (node (ref "R34") (pin "2") (pinfunction "2_2") (pintype "passive"))
      (node (ref "TP14") (pin "1") (pinfunction "G9_1") (pintype "passive"))
      (node (ref "U7") (pin "4") (pinfunction "VIN-_4") (pintype "input"))
      (node (ref "U8") (pin "1") (pinfunction "C_1") (pintype "passive"))
      (node (ref "U8") (pin "2") (pinfunction "REF_2") (pintype "passive"))
    )
    (net (code "25") (name "Net-(TP18-G9)") (class "Default")
      (node (ref "C23") (pin "2") (pinfunction "2_2") (pintype "passive"))
      (node (ref "R38") (pin "2") (pinfunction "2_2") (pintype "passive"))
      (node (ref "R41") (pin "1") (pinfunction "1_1") (pintype "passive"))
      (node (ref "R44") (pin "2") (pinfunction "2_2") (pintype "passive"))
      (node (ref "R45") (pin "2") (pinfunction "2_2") (pintype "passive"))
      (node (ref "R9") (pin "1") (pinfunction "1_1") (pintype "passive"))
      (node (ref "TP18") (pin "1") (pinfunction "G9_1") (pintype "passive"))
      (node (ref "U9") (pin "3") (pinfunction "VIN+_3") (pintype "input"))
      (node (ref "VD18") (pin "2") (pinfunction "C_2") (pintype "passive"))
      (node (ref "VD19") (pin "1") (pinfunction "C_1") (pintype "passive"))
    )
    (net (code "26") (name "Net-(TP20-G9)") (class "Default")
      (node (ref "C25") (pin "2") (pinfunction "2_2") (pintype "passive"))
      (node (ref "R43") (pin "2") (pinfunction "2_2") (pintype "passive"))
      (node (ref "R46") (pin "2") (pinfunction "2_2") (pintype "passive"))
      (node (ref "TP20") (pin "1") (pinfunction "G9_1") (pintype "passive"))
      (node (ref "U9") (pin "1") (pinfunction "VOUT_1") (pintype "output"))
    )
    (net (code "27") (name "Net-(TP21-G9)") (class "Default")
      (node (ref "C24") (pin "2") (pinfunction "2_2") (pintype "passive"))
      (node (ref "R40") (pin "1") (pinfunction "1_1") (pintype "passive"))
      (node (ref "R47") (pin "2") (pinfunction "2_2") (pintype "passive"))
      (node (ref "TP21") (pin "1") (pinfunction "G9_1") (pintype "passive"))
      (node (ref "U10") (pin "1") (pinfunction "C_1") (pintype "passive"))
      (node (ref "U10") (pin "2") (pinfunction "REF_2") (pintype "passive"))
      (node (ref "U9") (pin "4") (pinfunction "VIN-_4") (pintype "input"))
    )
  )
)
